# FPGAGTP.net
KiCad netlist of a schematic drawn in Altium Designer
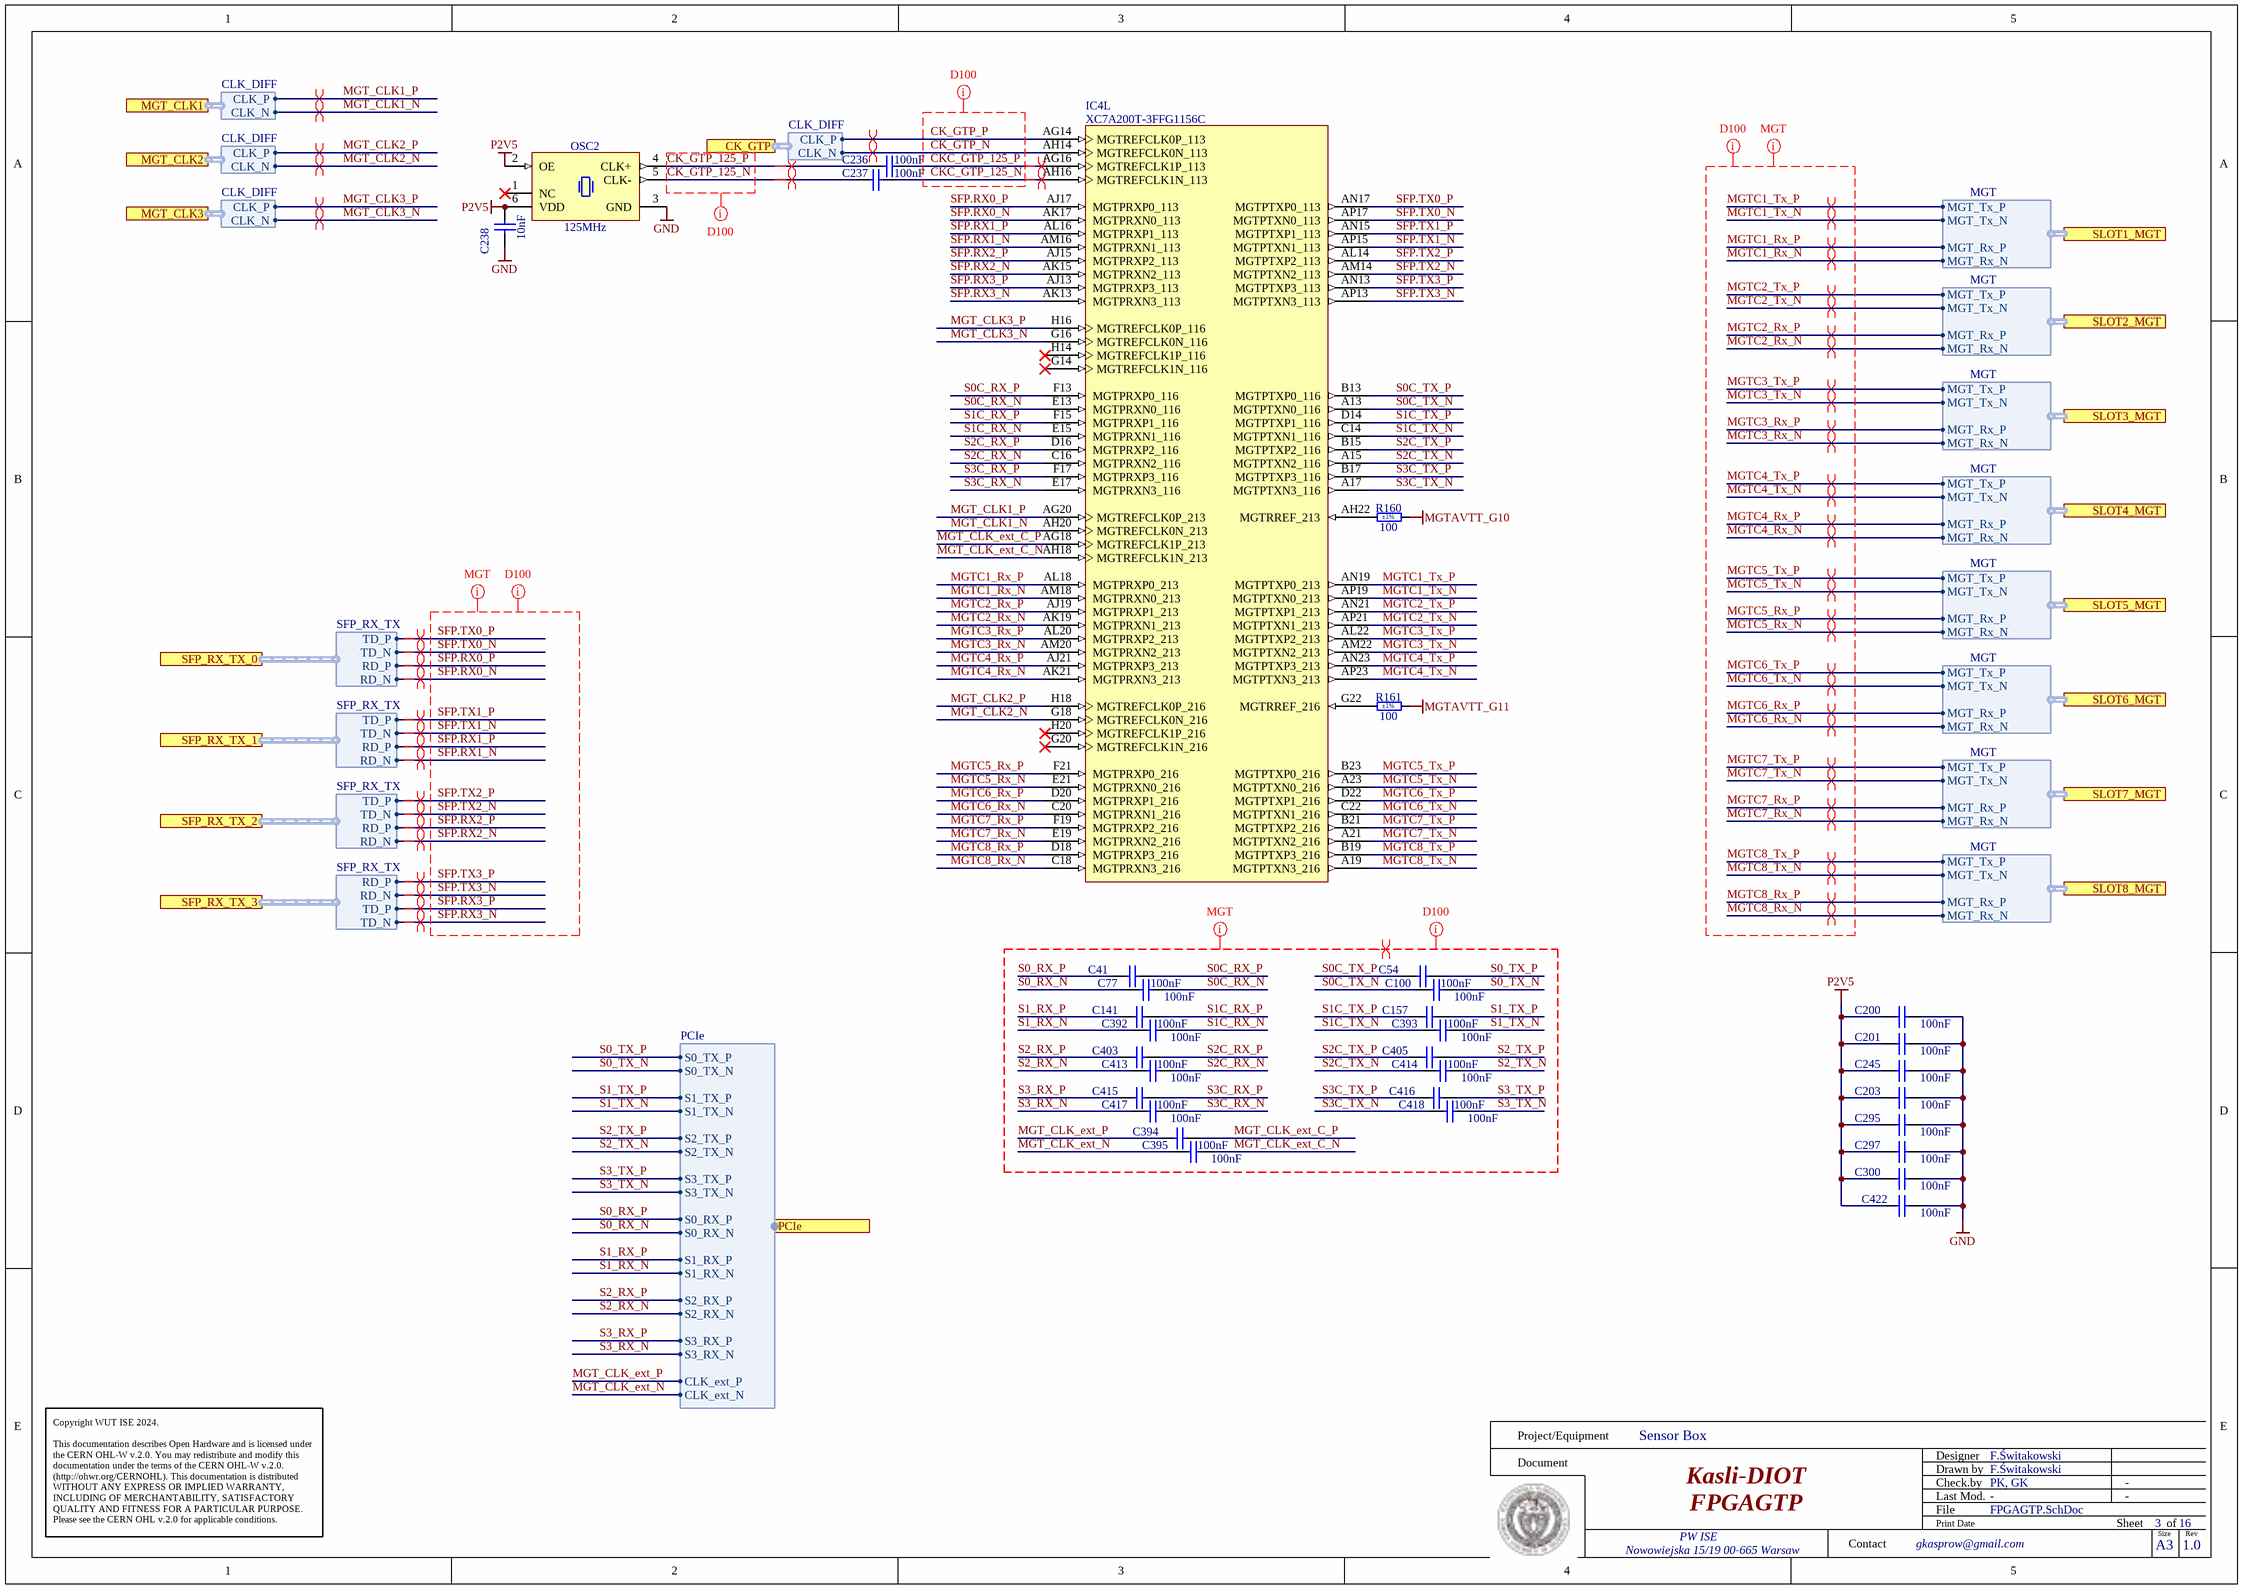
[diagram p0: FPGAGTP.SchDoc]

(export (version "E")
  (design (tool "Eeschema 10.0.6"))
  (components
    (comp (ref "C41")
      (value "100nF")
      (footprint "CAPC0603X33N")
      (description "Non-polarised capacitor")
      (fields
        (field (name "PART NUMBER") "CC0201_100NF_6.3V_10%_X5R")
        (field (name "VOLTAGE") "6.3V")
        (field (name "AUTHOR") "CERN DEM JLC")
      )
      (libsource (lib "Capacitors") (part "Capacitor - non polarized"))
    )
    (comp (ref "C54")
      (value "100nF")
      (footprint "CAPC0603X33N")
      (description "Non-polarised capacitor")
      (fields
        (field (name "PART NUMBER") "CC0201_100NF_6.3V_10%_X5R")
        (field (name "VOLTAGE") "6.3V")
        (field (name "AUTHOR") "CERN DEM JLC")
      )
      (libsource (lib "Capacitors") (part "Capacitor - non polarized"))
    )
    (comp (ref "C77")
      (value "100nF")
      (footprint "CAPC0603X33N")
      (description "Non-polarised capacitor")
      (fields
        (field (name "PART NUMBER") "CC0201_100NF_6.3V_10%_X5R")
        (field (name "VOLTAGE") "6.3V")
        (field (name "AUTHOR") "CERN DEM JLC")
      )
      (libsource (lib "Capacitors") (part "Capacitor - non polarized"))
    )
    (comp (ref "C100")
      (value "100nF")
      (footprint "CAPC0603X33N")
      (description "Non-polarised capacitor")
      (fields
        (field (name "PART NUMBER") "CC0201_100NF_6.3V_10%_X5R")
        (field (name "VOLTAGE") "6.3V")
        (field (name "AUTHOR") "CERN DEM JLC")
      )
      (libsource (lib "Capacitors") (part "Capacitor - non polarized"))
    )
    (comp (ref "C141")
      (value "100nF")
      (footprint "CAPC0603X33N")
      (description "Non-polarised capacitor")
      (fields
        (field (name "PART NUMBER") "CC0201_100NF_6.3V_10%_X5R")
        (field (name "VOLTAGE") "6.3V")
        (field (name "AUTHOR") "CERN DEM JLC")
      )
      (libsource (lib "Capacitors") (part "Capacitor - non polarized"))
    )
    (comp (ref "C157")
      (value "100nF")
      (footprint "CAPC0603X33N")
      (description "Non-polarised capacitor")
      (fields
        (field (name "PART NUMBER") "CC0201_100NF_6.3V_10%_X5R")
        (field (name "VOLTAGE") "6.3V")
        (field (name "AUTHOR") "CERN DEM JLC")
      )
      (libsource (lib "Capacitors") (part "Capacitor - non polarized"))
    )
    (comp (ref "C200")
      (value "100nF")
      (footprint "CAPC0603X33N")
      (description "Non-polarised capacitor")
      (fields
        (field (name "PART NUMBER") "CC0201_100NF_6.3V_10%_X5R")
        (field (name "VOLTAGE") "6.3V")
        (field (name "AUTHOR") "CERN DEM JLC")
      )
      (libsource (lib "Capacitors") (part "Capacitor - non polarized"))
    )
    (comp (ref "C201")
      (value "100nF")
      (footprint "CAPC0603X33N")
      (description "Non-polarised capacitor")
      (fields
        (field (name "PART NUMBER") "CC0201_100NF_6.3V_10%_X5R")
        (field (name "VOLTAGE") "6.3V")
        (field (name "AUTHOR") "CERN DEM JLC")
      )
      (libsource (lib "Capacitors") (part "Capacitor - non polarized"))
    )
    (comp (ref "C203")
      (value "100nF")
      (footprint "CAPC0603X33N")
      (description "Non-polarised capacitor")
      (fields
        (field (name "PART NUMBER") "CC0201_100NF_6.3V_10%_X5R")
        (field (name "VOLTAGE") "6.3V")
        (field (name "AUTHOR") "CERN DEM JLC")
      )
      (libsource (lib "Capacitors") (part "Capacitor - non polarized"))
    )
    (comp (ref "C236")
      (value "100nF")
      (footprint "CAPC0603X33N")
      (description "Non-polarised capacitor")
      (fields
        (field (name "PART NUMBER") "CC0201_100NF_6.3V_10%_X5R")
        (field (name "VOLTAGE") "6.3V")
        (field (name "AUTHOR") "CERN DEM JLC")
      )
      (libsource (lib "Capacitors") (part "Capacitor - non polarized"))
    )
    (comp (ref "C237")
      (value "100nF")
      (footprint "CAPC0603X33N")
      (description "Non-polarised capacitor")
      (fields
        (field (name "PART NUMBER") "CC0201_100NF_6.3V_10%_X5R")
        (field (name "VOLTAGE") "6.3V")
        (field (name "AUTHOR") "CERN DEM JLC")
      )
      (libsource (lib "Capacitors") (part "Capacitor - non polarized"))
    )
    (comp (ref "C238")
      (value "10nF")
      (footprint "CAPC1005X55N")
      (description "Non-polarised capacitor")
      (fields
        (field (name "PART NUMBER") "CC0402_10NF_16V_10%_X7R")
        (field (name "VOLTAGE") "16V")
        (field (name "AUTHOR") "CERN DEM JLC")
      )
      (libsource (lib "Capacitors") (part "Capacitor - non polarized"))
    )
    (comp (ref "C245")
      (value "100nF")
      (footprint "CAPC0603X33N")
      (description "Non-polarised capacitor")
      (fields
        (field (name "PART NUMBER") "CC0201_100NF_6.3V_10%_X5R")
        (field (name "VOLTAGE") "6.3V")
        (field (name "AUTHOR") "CERN DEM JLC")
      )
      (libsource (lib "Capacitors") (part "Capacitor - non polarized"))
    )
    (comp (ref "C295")
      (value "100nF")
      (footprint "CAPC0603X33N")
      (description "Non-polarised capacitor")
      (fields
        (field (name "PART NUMBER") "CC0201_100NF_6.3V_10%_X5R")
        (field (name "VOLTAGE") "6.3V")
        (field (name "AUTHOR") "CERN DEM JLC")
      )
      (libsource (lib "Capacitors") (part "Capacitor - non polarized"))
    )
    (comp (ref "C297")
      (value "100nF")
      (footprint "CAPC0603X33N")
      (description "Non-polarised capacitor")
      (fields
        (field (name "PART NUMBER") "CC0201_100NF_6.3V_10%_X5R")
        (field (name "VOLTAGE") "6.3V")
        (field (name "AUTHOR") "CERN DEM JLC")
      )
      (libsource (lib "Capacitors") (part "Capacitor - non polarized"))
    )
    (comp (ref "C300")
      (value "100nF")
      (footprint "CAPC0603X33N")
      (description "Non-polarised capacitor")
      (fields
        (field (name "PART NUMBER") "CC0201_100NF_6.3V_10%_X5R")
        (field (name "VOLTAGE") "6.3V")
        (field (name "AUTHOR") "CERN DEM JLC")
      )
      (libsource (lib "Capacitors") (part "Capacitor - non polarized"))
    )
    (comp (ref "C392")
      (value "100nF")
      (footprint "CAPC0603X33N")
      (description "Non-polarised capacitor")
      (fields
        (field (name "PART NUMBER") "CC0201_100NF_6.3V_10%_X5R")
        (field (name "VOLTAGE") "6.3V")
        (field (name "AUTHOR") "CERN DEM JLC")
      )
      (libsource (lib "Capacitors") (part "Capacitor - non polarized"))
    )
    (comp (ref "C393")
      (value "100nF")
      (footprint "CAPC0603X33N")
      (description "Non-polarised capacitor")
      (fields
        (field (name "PART NUMBER") "CC0201_100NF_6.3V_10%_X5R")
        (field (name "VOLTAGE") "6.3V")
        (field (name "AUTHOR") "CERN DEM JLC")
      )
      (libsource (lib "Capacitors") (part "Capacitor - non polarized"))
    )
    (comp (ref "C394")
      (value "100nF")
      (footprint "CAPC0603X33N")
      (description "Non-polarised capacitor")
      (fields
        (field (name "PART NUMBER") "CC0201_100NF_6.3V_10%_X5R")
        (field (name "VOLTAGE") "6.3V")
        (field (name "AUTHOR") "CERN DEM JLC")
      )
      (libsource (lib "Capacitors") (part "Capacitor - non polarized"))
    )
    (comp (ref "C395")
      (value "100nF")
      (footprint "CAPC0603X33N")
      (description "Non-polarised capacitor")
      (fields
        (field (name "PART NUMBER") "CC0201_100NF_6.3V_10%_X5R")
        (field (name "VOLTAGE") "6.3V")
        (field (name "AUTHOR") "CERN DEM JLC")
      )
      (libsource (lib "Capacitors") (part "Capacitor - non polarized"))
    )
    (comp (ref "C403")
      (value "100nF")
      (footprint "CAPC0603X33N")
      (description "Non-polarised capacitor")
      (fields
        (field (name "PART NUMBER") "CC0201_100NF_6.3V_10%_X5R")
        (field (name "VOLTAGE") "6.3V")
        (field (name "AUTHOR") "CERN DEM JLC")
      )
      (libsource (lib "Capacitors") (part "Capacitor - non polarized"))
    )
    (comp (ref "C405")
      (value "100nF")
      (footprint "CAPC0603X33N")
      (description "Non-polarised capacitor")
      (fields
        (field (name "PART NUMBER") "CC0201_100NF_6.3V_10%_X5R")
        (field (name "VOLTAGE") "6.3V")
        (field (name "AUTHOR") "CERN DEM JLC")
      )
      (libsource (lib "Capacitors") (part "Capacitor - non polarized"))
    )
    (comp (ref "C413")
      (value "100nF")
      (footprint "CAPC0603X33N")
      (description "Non-polarised capacitor")
      (fields
        (field (name "PART NUMBER") "CC0201_100NF_6.3V_10%_X5R")
        (field (name "VOLTAGE") "6.3V")
        (field (name "AUTHOR") "CERN DEM JLC")
      )
      (libsource (lib "Capacitors") (part "Capacitor - non polarized"))
    )
    (comp (ref "C414")
      (value "100nF")
      (footprint "CAPC0603X33N")
      (description "Non-polarised capacitor")
      (fields
        (field (name "PART NUMBER") "CC0201_100NF_6.3V_10%_X5R")
        (field (name "VOLTAGE") "6.3V")
        (field (name "AUTHOR") "CERN DEM JLC")
      )
      (libsource (lib "Capacitors") (part "Capacitor - non polarized"))
    )
    (comp (ref "C415")
      (value "100nF")
      (footprint "CAPC0603X33N")
      (description "Non-polarised capacitor")
      (fields
        (field (name "PART NUMBER") "CC0201_100NF_6.3V_10%_X5R")
        (field (name "VOLTAGE") "6.3V")
        (field (name "AUTHOR") "CERN DEM JLC")
      )
      (libsource (lib "Capacitors") (part "Capacitor - non polarized"))
    )
    (comp (ref "C416")
      (value "100nF")
      (footprint "CAPC0603X33N")
      (description "Non-polarised capacitor")
      (fields
        (field (name "PART NUMBER") "CC0201_100NF_6.3V_10%_X5R")
        (field (name "VOLTAGE") "6.3V")
        (field (name "AUTHOR") "CERN DEM JLC")
      )
      (libsource (lib "Capacitors") (part "Capacitor - non polarized"))
    )
    (comp (ref "C417")
      (value "100nF")
      (footprint "CAPC0603X33N")
      (description "Non-polarised capacitor")
      (fields
        (field (name "PART NUMBER") "CC0201_100NF_6.3V_10%_X5R")
        (field (name "VOLTAGE") "6.3V")
        (field (name "AUTHOR") "CERN DEM JLC")
      )
      (libsource (lib "Capacitors") (part "Capacitor - non polarized"))
    )
    (comp (ref "C418")
      (value "100nF")
      (footprint "CAPC0603X33N")
      (description "Non-polarised capacitor")
      (fields
        (field (name "PART NUMBER") "CC0201_100NF_6.3V_10%_X5R")
        (field (name "VOLTAGE") "6.3V")
        (field (name "AUTHOR") "CERN DEM JLC")
      )
      (libsource (lib "Capacitors") (part "Capacitor - non polarized"))
    )
    (comp (ref "C422")
      (value "100nF")
      (footprint "CAPC0603X33N")
      (description "Non-polarised capacitor")
      (fields
        (field (name "PART NUMBER") "CC0201_100NF_6.3V_10%_X5R")
        (field (name "VOLTAGE") "6.3V")
        (field (name "AUTHOR") "CERN DEM JLC")
      )
      (libsource (lib "Capacitors") (part "Capacitor - non polarized"))
    )
    (comp (ref "IC4")
      (value "XC7A200T-3FFG1156C")
      (footprint "BGA1156C100P34X34_3500X3500X310")
      (description "Artix-7 FPGA, 500 User I/Os, 16 GTP, 1156-Ball BGA, , Speed Grade 3, Commercial Grade, Pb-Free")
      (fields (field (name "MANUFACTURER") "XILINX") (field (name "AUTHOR") "CERN DEM JLC"))
      (libsource (lib "ICs And Semiconductors") (part "XC7A200T-3FFG1156C"))
    )
    (comp (ref "OSC2")
      (value "125MHz")
      (footprint "OSC_SILICON-LAB_SI510-6N")
      (description "Crystal Oscillator 6 pins, Si510 (LVDS/LVPECL/HCSL/Dual CMOS)")
      (fields
        (field (name "PART NUMBER") "OSC_125MHZ_SILICON-LAB_510FBA125M000AAG")
        (field (name "MANUFACTURER") "SILICON LABS")
        (field (name "AUTHOR") "CERN DEM JMW")
      )
      (libsource (lib "ICs And Semiconductors") (part "Oscillator SILICON-LAB_Si510-6N"))
    )
    (comp (ref "R160")
      (value "100")
      (footprint "RESC0603X28N")
      (description "Resistor - 1%")
      (fields
        (field (name "TOLERANCE") "±1%")
        (field (name "PART NUMBER") "R0201_100R_1%_0.05W_200PPM")
        (field (name "POWER") "0.05W")
        (field (name "AUTHOR") "CERN DEM JLC")
      )
      (libsource (lib "Resistors") (part "Resistor - 1%"))
    )
    (comp (ref "R161")
      (value "100")
      (footprint "RESC0603X28N")
      (description "Resistor - 1%")
      (fields
        (field (name "TOLERANCE") "±1%")
        (field (name "PART NUMBER") "R0201_100R_1%_0.05W_200PPM")
        (field (name "POWER") "0.05W")
        (field (name "AUTHOR") "CERN DEM JLC")
      )
      (libsource (lib "Resistors") (part "Resistor - 1%"))
    )
  )
  (nets
    (net (code "5") (name "/CKC_GTP_125_N") (class "Default")
      (node (ref "C237") (pin "2") (pinfunction "2_2") (pintype "passive"))
      (node (ref "IC4") (pin "AH16") (pinfunction "MGTREFCLK1N_113_AH16") (pintype "input"))
    )
    (net (code "6") (name "/CKC_GTP_125_P") (class "Default")
      (node (ref "C236") (pin "2") (pinfunction "2_2") (pintype "passive"))
      (node (ref "IC4") (pin "AG16") (pinfunction "MGTREFCLK1P_113_AG16") (pintype "input"))
    )
    (net (code "7") (name "/CK_GTP_125_N") (class "Default")
      (node (ref "C237") (pin "1") (pinfunction "1_1") (pintype "passive"))
      (node (ref "OSC2") (pin "5") (pinfunction "CLK-_5") (pintype "output"))
    )
    (net (code "8") (name "/CK_GTP_125_P") (class "Default")
      (node (ref "C236") (pin "1") (pinfunction "1_1") (pintype "passive"))
      (node (ref "OSC2") (pin "4") (pinfunction "CLK+_4") (pintype "output"))
    )
    (net (code "9") (name "/CK_GTP_N") (class "Default")
      (node (ref "IC4") (pin "AH14") (pinfunction "MGTREFCLK0N_113_AH14") (pintype "input"))
    )
    (net (code "10") (name "/CK_GTP_P") (class "Default")
      (node (ref "IC4") (pin "AG14") (pinfunction "MGTREFCLK0P_113_AG14") (pintype "input"))
    )
    (net (code "11") (name "/MGTC1_Rx_N") (class "Default")
      (node (ref "IC4") (pin "AM18") (pinfunction "MGTPRXN0_213_AM18") (pintype "input"))
    )
    (net (code "12") (name "/MGTC1_Rx_P") (class "Default")
      (node (ref "IC4") (pin "AL18") (pinfunction "MGTPRXP0_213_AL18") (pintype "input"))
    )
    (net (code "13") (name "/MGTC1_Tx_N") (class "Default")
      (node (ref "IC4") (pin "AP19") (pinfunction "MGTPTXN0_213_AP19") (pintype "output"))
    )
    (net (code "14") (name "/MGTC1_Tx_P") (class "Default")
      (node (ref "IC4") (pin "AN19") (pinfunction "MGTPTXP0_213_AN19") (pintype "output"))
    )
    (net (code "15") (name "/MGTC2_Rx_N") (class "Default")
      (node (ref "IC4") (pin "AK19") (pinfunction "MGTPRXN1_213_AK19") (pintype "input"))
    )
    (net (code "16") (name "/MGTC2_Rx_P") (class "Default")
      (node (ref "IC4") (pin "AJ19") (pinfunction "MGTPRXP1_213_AJ19") (pintype "input"))
    )
    (net (code "17") (name "/MGTC2_Tx_N") (class "Default")
      (node (ref "IC4") (pin "AP21") (pinfunction "MGTPTXN1_213_AP21") (pintype "output"))
    )
    (net (code "18") (name "/MGTC2_Tx_P") (class "Default")
      (node (ref "IC4") (pin "AN21") (pinfunction "MGTPTXP1_213_AN21") (pintype "output"))
    )
    (net (code "19") (name "/MGTC3_Rx_N") (class "Default")
      (node (ref "IC4") (pin "AM20") (pinfunction "MGTPRXN2_213_AM20") (pintype "input"))
    )
    (net (code "20") (name "/MGTC3_Rx_P") (class "Default")
      (node (ref "IC4") (pin "AL20") (pinfunction "MGTPRXP2_213_AL20") (pintype "input"))
    )
    (net (code "21") (name "/MGTC3_Tx_N") (class "Default")
      (node (ref "IC4") (pin "AM22") (pinfunction "MGTPTXN2_213_AM22") (pintype "output"))
    )
    (net (code "22") (name "/MGTC3_Tx_P") (class "Default")
      (node (ref "IC4") (pin "AL22") (pinfunction "MGTPTXP2_213_AL22") (pintype "output"))
    )
    (net (code "23") (name "/MGTC4_Rx_N") (class "Default")
      (node (ref "IC4") (pin "AK21") (pinfunction "MGTPRXN3_213_AK21") (pintype "input"))
    )
    (net (code "24") (name "/MGTC4_Rx_P") (class "Default")
      (node (ref "IC4") (pin "AJ21") (pinfunction "MGTPRXP3_213_AJ21") (pintype "input"))
    )
    (net (code "25") (name "/MGTC4_Tx_N") (class "Default")
      (node (ref "IC4") (pin "AP23") (pinfunction "MGTPTXN3_213_AP23") (pintype "output"))
    )
    (net (code "26") (name "/MGTC4_Tx_P") (class "Default")
      (node (ref "IC4") (pin "AN23") (pinfunction "MGTPTXP3_213_AN23") (pintype "output"))
    )
    (net (code "27") (name "/MGTC5_Rx_N") (class "Default")
      (node (ref "IC4") (pin "E21") (pinfunction "MGTPRXN0_216_E21") (pintype "input"))
    )
    (net (code "28") (name "/MGTC5_Rx_P") (class "Default")
      (node (ref "IC4") (pin "F21") (pinfunction "MGTPRXP0_216_F21") (pintype "input"))
    )
    (net (code "29") (name "/MGTC5_Tx_N") (class "Default")
      (node (ref "IC4") (pin "A23") (pinfunction "MGTPTXN0_216_A23") (pintype "output"))
    )
    (net (code "30") (name "/MGTC5_Tx_P") (class "Default")
      (node (ref "IC4") (pin "B23") (pinfunction "MGTPTXP0_216_B23") (pintype "output"))
    )
    (net (code "31") (name "/MGTC6_Rx_N") (class "Default")
      (node (ref "IC4") (pin "C20") (pinfunction "MGTPRXN1_216_C20") (pintype "input"))
    )
    (net (code "32") (name "/MGTC6_Rx_P") (class "Default")
      (node (ref "IC4") (pin "D20") (pinfunction "MGTPRXP1_216_D20") (pintype "input"))
    )
    (net (code "33") (name "/MGTC6_Tx_N") (class "Default")
      (node (ref "IC4") (pin "C22") (pinfunction "MGTPTXN1_216_C22") (pintype "output"))
    )
    (net (code "34") (name "/MGTC6_Tx_P") (class "Default")
      (node (ref "IC4") (pin "D22") (pinfunction "MGTPTXP1_216_D22") (pintype "output"))
    )
    (net (code "35") (name "/MGTC7_Rx_N") (class "Default")
      (node (ref "IC4") (pin "E19") (pinfunction "MGTPRXN2_216_E19") (pintype "input"))
    )
    (net (code "36") (name "/MGTC7_Rx_P") (class "Default")
      (node (ref "IC4") (pin "F19") (pinfunction "MGTPRXP2_216_F19") (pintype "input"))
    )
    (net (code "37") (name "/MGTC7_Tx_N") (class "Default")
      (node (ref "IC4") (pin "A21") (pinfunction "MGTPTXN2_216_A21") (pintype "output"))
    )
    (net (code "38") (name "/MGTC7_Tx_P") (class "Default")
      (node (ref "IC4") (pin "B21") (pinfunction "MGTPTXP2_216_B21") (pintype "output"))
    )
    (net (code "39") (name "/MGTC8_Rx_N") (class "Default")
      (node (ref "IC4") (pin "C18") (pinfunction "MGTPRXN3_216_C18") (pintype "input"))
    )
    (net (code "40") (name "/MGTC8_Rx_P") (class "Default")
      (node (ref "IC4") (pin "D18") (pinfunction "MGTPRXP3_216_D18") (pintype "input"))
    )
    (net (code "41") (name "/MGTC8_Tx_N") (class "Default")
      (node (ref "IC4") (pin "A19") (pinfunction "MGTPTXN3_216_A19") (pintype "output"))
    )
    (net (code "42") (name "/MGTC8_Tx_P") (class "Default")
      (node (ref "IC4") (pin "B19") (pinfunction "MGTPTXP3_216_B19") (pintype "output"))
    )
    (net (code "43") (name "/MGT_CLK1_N") (class "Default")
      (node (ref "IC4") (pin "AH20") (pinfunction "MGTREFCLK0N_213_AH20") (pintype "input"))
    )
    (net (code "44") (name "/MGT_CLK1_P") (class "Default")
      (node (ref "IC4") (pin "AG20") (pinfunction "MGTREFCLK0P_213_AG20") (pintype "input"))
    )
    (net (code "45") (name "/MGT_CLK2_N") (class "Default")
      (node (ref "IC4") (pin "G18") (pinfunction "MGTREFCLK0N_216_G18") (pintype "input"))
    )
    (net (code "46") (name "/MGT_CLK2_P") (class "Default")
      (node (ref "IC4") (pin "H18") (pinfunction "MGTREFCLK0P_216_H18") (pintype "input"))
    )
    (net (code "47") (name "/MGT_CLK3_N") (class "Default")
      (node (ref "IC4") (pin "G16") (pinfunction "MGTREFCLK0N_116_G16") (pintype "input"))
    )
    (net (code "48") (name "/MGT_CLK3_P") (class "Default")
      (node (ref "IC4") (pin "H16") (pinfunction "MGTREFCLK0P_116_H16") (pintype "input"))
    )
    (net (code "49") (name "/MGT_CLK_ext_C_N") (class "Default")
      (node (ref "C395") (pin "2") (pinfunction "2_2") (pintype "passive"))
      (node (ref "IC4") (pin "AH18") (pinfunction "MGTREFCLK1N_213_AH18") (pintype "input"))
    )
    (net (code "50") (name "/MGT_CLK_ext_C_P") (class "Default")
      (node (ref "C394") (pin "2") (pinfunction "2_2") (pintype "passive"))
      (node (ref "IC4") (pin "AG18") (pinfunction "MGTREFCLK1P_213_AG18") (pintype "input"))
    )
    (net (code "51") (name "/MGT_CLK_ext_N") (class "Default")
      (node (ref "C395") (pin "1") (pinfunction "1_1") (pintype "passive"))
    )
    (net (code "52") (name "/MGT_CLK_ext_P") (class "Default")
      (node (ref "C394") (pin "1") (pinfunction "1_1") (pintype "passive"))
    )
    (net (code "53") (name "/S0C_RX_N") (class "Default")
      (node (ref "C77") (pin "2") (pinfunction "2_2") (pintype "passive"))
      (node (ref "IC4") (pin "E13") (pinfunction "MGTPRXN0_116_E13") (pintype "input"))
    )
    (net (code "54") (name "/S0C_RX_P") (class "Default")
      (node (ref "C41") (pin "2") (pinfunction "2_2") (pintype "passive"))
      (node (ref "IC4") (pin "F13") (pinfunction "MGTPRXP0_116_F13") (pintype "input"))
    )
    (net (code "55") (name "/S0C_TX_N") (class "Default")
      (node (ref "C100") (pin "1") (pinfunction "1_1") (pintype "passive"))
      (node (ref "IC4") (pin "A13") (pinfunction "MGTPTXN0_116_A13") (pintype "output"))
    )
    (net (code "56") (name "/S0C_TX_P") (class "Default")
      (node (ref "C54") (pin "1") (pinfunction "1_1") (pintype "passive"))
      (node (ref "IC4") (pin "B13") (pinfunction "MGTPTXP0_116_B13") (pintype "output"))
    )
    (net (code "57") (name "/S0_RX_N") (class "Default")
      (node (ref "C77") (pin "1") (pinfunction "1_1") (pintype "passive"))
    )
    (net (code "58") (name "/S0_RX_P") (class "Default")
      (node (ref "C41") (pin "1") (pinfunction "1_1") (pintype "passive"))
    )
    (net (code "59") (name "/S0_TX_N") (class "Default")
      (node (ref "C100") (pin "2") (pinfunction "2_2") (pintype "passive"))
    )
    (net (code "60") (name "/S0_TX_P") (class "Default")
      (node (ref "C54") (pin "2") (pinfunction "2_2") (pintype "passive"))
    )
    (net (code "61") (name "/S1C_RX_N") (class "Default")
      (node (ref "C392") (pin "2") (pinfunction "2_2") (pintype "passive"))
      (node (ref "IC4") (pin "E15") (pinfunction "MGTPRXN1_116_E15") (pintype "input"))
    )
    (net (code "62") (name "/S1C_RX_P") (class "Default")
      (node (ref "C141") (pin "2") (pinfunction "2_2") (pintype "passive"))
      (node (ref "IC4") (pin "F15") (pinfunction "MGTPRXP1_116_F15") (pintype "input"))
    )
    (net (code "63") (name "/S1C_TX_N") (class "Default")
      (node (ref "C393") (pin "1") (pinfunction "1_1") (pintype "passive"))
      (node (ref "IC4") (pin "C14") (pinfunction "MGTPTXN1_116_C14") (pintype "output"))
    )
    (net (code "64") (name "/S1C_TX_P") (class "Default")
      (node (ref "C157") (pin "1") (pinfunction "1_1") (pintype "passive"))
      (node (ref "IC4") (pin "D14") (pinfunction "MGTPTXP1_116_D14") (pintype "output"))
    )
    (net (code "65") (name "/S1_RX_N") (class "Default")
      (node (ref "C392") (pin "1") (pinfunction "1_1") (pintype "passive"))
    )
    (net (code "66") (name "/S1_RX_P") (class "Default")
      (node (ref "C141") (pin "1") (pinfunction "1_1") (pintype "passive"))
    )
    (net (code "67") (name "/S1_TX_N") (class "Default")
      (node (ref "C393") (pin "2") (pinfunction "2_2") (pintype "passive"))
    )
    (net (code "68") (name "/S1_TX_P") (class "Default")
      (node (ref "C157") (pin "2") (pinfunction "2_2") (pintype "passive"))
    )
    (net (code "69") (name "/S2C_RX_N") (class "Default")
      (node (ref "C413") (pin "2") (pinfunction "2_2") (pintype "passive"))
      (node (ref "IC4") (pin "C16") (pinfunction "MGTPRXN2_116_C16") (pintype "input"))
    )
    (net (code "70") (name "/S2C_RX_P") (class "Default")
      (node (ref "C403") (pin "2") (pinfunction "2_2") (pintype "passive"))
      (node (ref "IC4") (pin "D16") (pinfunction "MGTPRXP2_116_D16") (pintype "input"))
    )
    (net (code "71") (name "/S2C_TX_N") (class "Default")
      (node (ref "C414") (pin "1") (pinfunction "1_1") (pintype "passive"))
      (node (ref "IC4") (pin "A15") (pinfunction "MGTPTXN2_116_A15") (pintype "output"))
    )
    (net (code "72") (name "/S2C_TX_P") (class "Default")
      (node (ref "C405") (pin "1") (pinfunction "1_1") (pintype "passive"))
      (node (ref "IC4") (pin "B15") (pinfunction "MGTPTXP2_116_B15") (pintype "output"))
    )
    (net (code "73") (name "/S2_RX_N") (class "Default")
      (node (ref "C413") (pin "1") (pinfunction "1_1") (pintype "passive"))
    )
    (net (code "74") (name "/S2_RX_P") (class "Default")
      (node (ref "C403") (pin "1") (pinfunction "1_1") (pintype "passive"))
    )
    (net (code "75") (name "/S2_TX_N") (class "Default")
      (node (ref "C414") (pin "2") (pinfunction "2_2") (pintype "passive"))
    )
    (net (code "76") (name "/S2_TX_P") (class "Default")
      (node (ref "C405") (pin "2") (pinfunction "2_2") (pintype "passive"))
    )
    (net (code "77") (name "/S3C_RX_N") (class "Default")
      (node (ref "C417") (pin "2") (pinfunction "2_2") (pintype "passive"))
      (node (ref "IC4") (pin "E17") (pinfunction "MGTPRXN3_116_E17") (pintype "input"))
    )
    (net (code "78") (name "/S3C_RX_P") (class "Default")
      (node (ref "C415") (pin "2") (pinfunction "2_2") (pintype "passive"))
      (node (ref "IC4") (pin "F17") (pinfunction "MGTPRXP3_116_F17") (pintype "input"))
    )
    (net (code "79") (name "/S3C_TX_N") (class "Default")
      (node (ref "C418") (pin "1") (pinfunction "1_1") (pintype "passive"))
      (node (ref "IC4") (pin "A17") (pinfunction "MGTPTXN3_116_A17") (pintype "output"))
    )
    (net (code "80") (name "/S3C_TX_P") (class "Default")
      (node (ref "C416") (pin "1") (pinfunction "1_1") (pintype "passive"))
      (node (ref "IC4") (pin "B17") (pinfunction "MGTPTXP3_116_B17") (pintype "output"))
    )
    (net (code "81") (name "/S3_RX_N") (class "Default")
      (node (ref "C417") (pin "1") (pinfunction "1_1") (pintype "passive"))
    )
    (net (code "82") (name "/S3_RX_P") (class "Default")
      (node (ref "C415") (pin "1") (pinfunction "1_1") (pintype "passive"))
    )
    (net (code "83") (name "/S3_TX_N") (class "Default")
      (node (ref "C418") (pin "2") (pinfunction "2_2") (pintype "passive"))
    )
    (net (code "84") (name "/S3_TX_P") (class "Default")
      (node (ref "C416") (pin "2") (pinfunction "2_2") (pintype "passive"))
    )
    (net (code "85") (name "/SFP.RX0_N") (class "Default")
      (node (ref "IC4") (pin "AK17") (pinfunction "MGTPRXN0_113_AK17") (pintype "input"))
    )
    (net (code "86") (name "/SFP.RX0_P") (class "Default")
      (node (ref "IC4") (pin "AJ17") (pinfunction "MGTPRXP0_113_AJ17") (pintype "input"))
    )
    (net (code "87") (name "/SFP.RX1_N") (class "Default")
      (node (ref "IC4") (pin "AM16") (pinfunction "MGTPRXN1_113_AM16") (pintype "input"))
    )
    (net (code "88") (name "/SFP.RX1_P") (class "Default")
      (node (ref "IC4") (pin "AL16") (pinfunction "MGTPRXP1_113_AL16") (pintype "input"))
    )
    (net (code "89") (name "/SFP.RX2_N") (class "Default")
      (node (ref "IC4") (pin "AK15") (pinfunction "MGTPRXN2_113_AK15") (pintype "input"))
    )
    (net (code "90") (name "/SFP.RX2_P") (class "Default")
      (node (ref "IC4") (pin "AJ15") (pinfunction "MGTPRXP2_113_AJ15") (pintype "input"))
    )
    (net (code "91") (name "/SFP.RX3_N") (class "Default")
      (node (ref "IC4") (pin "AK13") (pinfunction "MGTPRXN3_113_AK13") (pintype "input"))
    )
    (net (code "92") (name "/SFP.RX3_P") (class "Default")
      (node (ref "IC4") (pin "AJ13") (pinfunction "MGTPRXP3_113_AJ13") (pintype "input"))
    )
    (net (code "93") (name "/SFP.TX0_N") (class "Default")
      (node (ref "IC4") (pin "AP17") (pinfunction "MGTPTXN0_113_AP17") (pintype "output"))
    )
    (net (code "94") (name "/SFP.TX0_P") (class "Default")
      (node (ref "IC4") (pin "AN17") (pinfunction "MGTPTXP0_113_AN17") (pintype "output"))
    )
    (net (code "95") (name "/SFP.TX1_N") (class "Default")
      (node (ref "IC4") (pin "AP15") (pinfunction "MGTPTXN1_113_AP15") (pintype "output"))
    )
    (net (code "96") (name "/SFP.TX1_P") (class "Default")
      (node (ref "IC4") (pin "AN15") (pinfunction "MGTPTXP1_113_AN15") (pintype "output"))
    )
    (net (code "97") (name "/SFP.TX2_N") (class "Default")
      (node (ref "IC4") (pin "AM14") (pinfunction "MGTPTXN2_113_AM14") (pintype "output"))
    )
    (net (code "98") (name "/SFP.TX2_P") (class "Default")
      (node (ref "IC4") (pin "AL14") (pinfunction "MGTPTXP2_113_AL14") (pintype "output"))
    )
    (net (code "99") (name "/SFP.TX3_N") (class "Default")
      (node (ref "IC4") (pin "AP13") (pinfunction "MGTPTXN3_113_AP13") (pintype "output"))
    )
    (net (code "100") (name "/SFP.TX3_P") (class "Default")
      (node (ref "IC4") (pin "AN13") (pinfunction "MGTPTXP3_113_AN13") (pintype "output"))
    )
    (net (code "105") (name "GND") (class "Default")
      (node (ref "C200") (pin "2") (pinfunction "2_2") (pintype "passive"))
      (node (ref "C201") (pin "2") (pinfunction "2_2") (pintype "passive"))
      (node (ref "C203") (pin "2") (pinfunction "2_2") (pintype "passive"))
      (node (ref "C238") (pin "1") (pinfunction "1_1") (pintype "passive"))
      (node (ref "C245") (pin "2") (pinfunction "2_2") (pintype "passive"))
      (node (ref "C295") (pin "2") (pinfunction "2_2") (pintype "passive"))
      (node (ref "C297") (pin "2") (pinfunction "2_2") (pintype "passive"))
      (node (ref "C300") (pin "2") (pinfunction "2_2") (pintype "passive"))
      (node (ref "C422") (pin "2") (pinfunction "2_2") (pintype "passive"))
      (node (ref "OSC2") (pin "3") (pinfunction "GND_3") (pintype "power_in"))
    )
    (net (code "106") (name "MGTAVTT_G10") (class "Default")
      (node (ref "R160") (pin "2") (pinfunction "2_2") (pintype "passive"))
    )
    (net (code "107") (name "MGTAVTT_G11") (class "Default")
      (node (ref "R161") (pin "2") (pinfunction "2_2") (pintype "passive"))
    )
    (net (code "108") (name "Net-(IC4L-MGTRREF_213)") (class "Default")
      (node (ref "IC4") (pin "AH22") (pinfunction "MGTRREF_213_AH22") (pintype "input"))
      (node (ref "R160") (pin "1") (pinfunction "1_1") (pintype "passive"))
    )
    (net (code "109") (name "Net-(IC4L-MGTRREF_216)") (class "Default")
      (node (ref "IC4") (pin "G22") (pinfunction "MGTRREF_216_G22") (pintype "input"))
      (node (ref "R161") (pin "1") (pinfunction "1_1") (pintype "passive"))
    )
    (net (code "110") (name "P2V5") (class "Default")
      (node (ref "C200") (pin "1") (pinfunction "1_1") (pintype "passive"))
      (node (ref "C201") (pin "1") (pinfunction "1_1") (pintype "passive"))
      (node (ref "C203") (pin "1") (pinfunction "1_1") (pintype "passive"))
      (node (ref "C238") (pin "2") (pinfunction "2_2") (pintype "passive"))
      (node (ref "C245") (pin "1") (pinfunction "1_1") (pintype "passive"))
      (node (ref "C295") (pin "1") (pinfunction "1_1") (pintype "passive"))
      (node (ref "C297") (pin "1") (pinfunction "1_1") (pintype "passive"))
      (node (ref "C300") (pin "1") (pinfunction "1_1") (pintype "passive"))
      (node (ref "C422") (pin "1") (pinfunction "1_1") (pintype "passive"))
      (node (ref "OSC2") (pin "2") (pinfunction "OE_2") (pintype "input"))
      (node (ref "OSC2") (pin "6") (pinfunction "VDD_6") (pintype "power_in"))
    )
    (net (code "111") (name "unconnected-(IC4L-MGTREFCLK1N_116-PadG14)") (class "Default")
      (node (ref "IC4") (pin "G14") (pinfunction "MGTREFCLK1N_116_G14") (pintype "input+no_connect"))
    )
    (net (code "112") (name "unconnected-(IC4L-MGTREFCLK1N_216-PadG20)") (class "Default")
      (node (ref "IC4") (pin "G20") (pinfunction "MGTREFCLK1N_216_G20") (pintype "input+no_connect"))
    )
    (net (code "113") (name "unconnected-(IC4L-MGTREFCLK1P_116-PadH14)") (class "Default")
      (node (ref "IC4") (pin "H14") (pinfunction "MGTREFCLK1P_116_H14") (pintype "input+no_connect"))
    )
    (net (code "114") (name "unconnected-(IC4L-MGTREFCLK1P_216-PadH20)") (class "Default")
      (node (ref "IC4") (pin "H20") (pinfunction "MGTREFCLK1P_216_H20") (pintype "input+no_connect"))
    )
    (net (code "115") (name "unconnected-(OSC2-NC-Pad1)") (class "Default")
      (node (ref "OSC2") (pin "1") (pinfunction "NC_1") (pintype "passive+no_connect"))
    )
  )
)
